# Alarm_Controller_v3.net
KiCad netlist of a schematic drawn in EAGLE
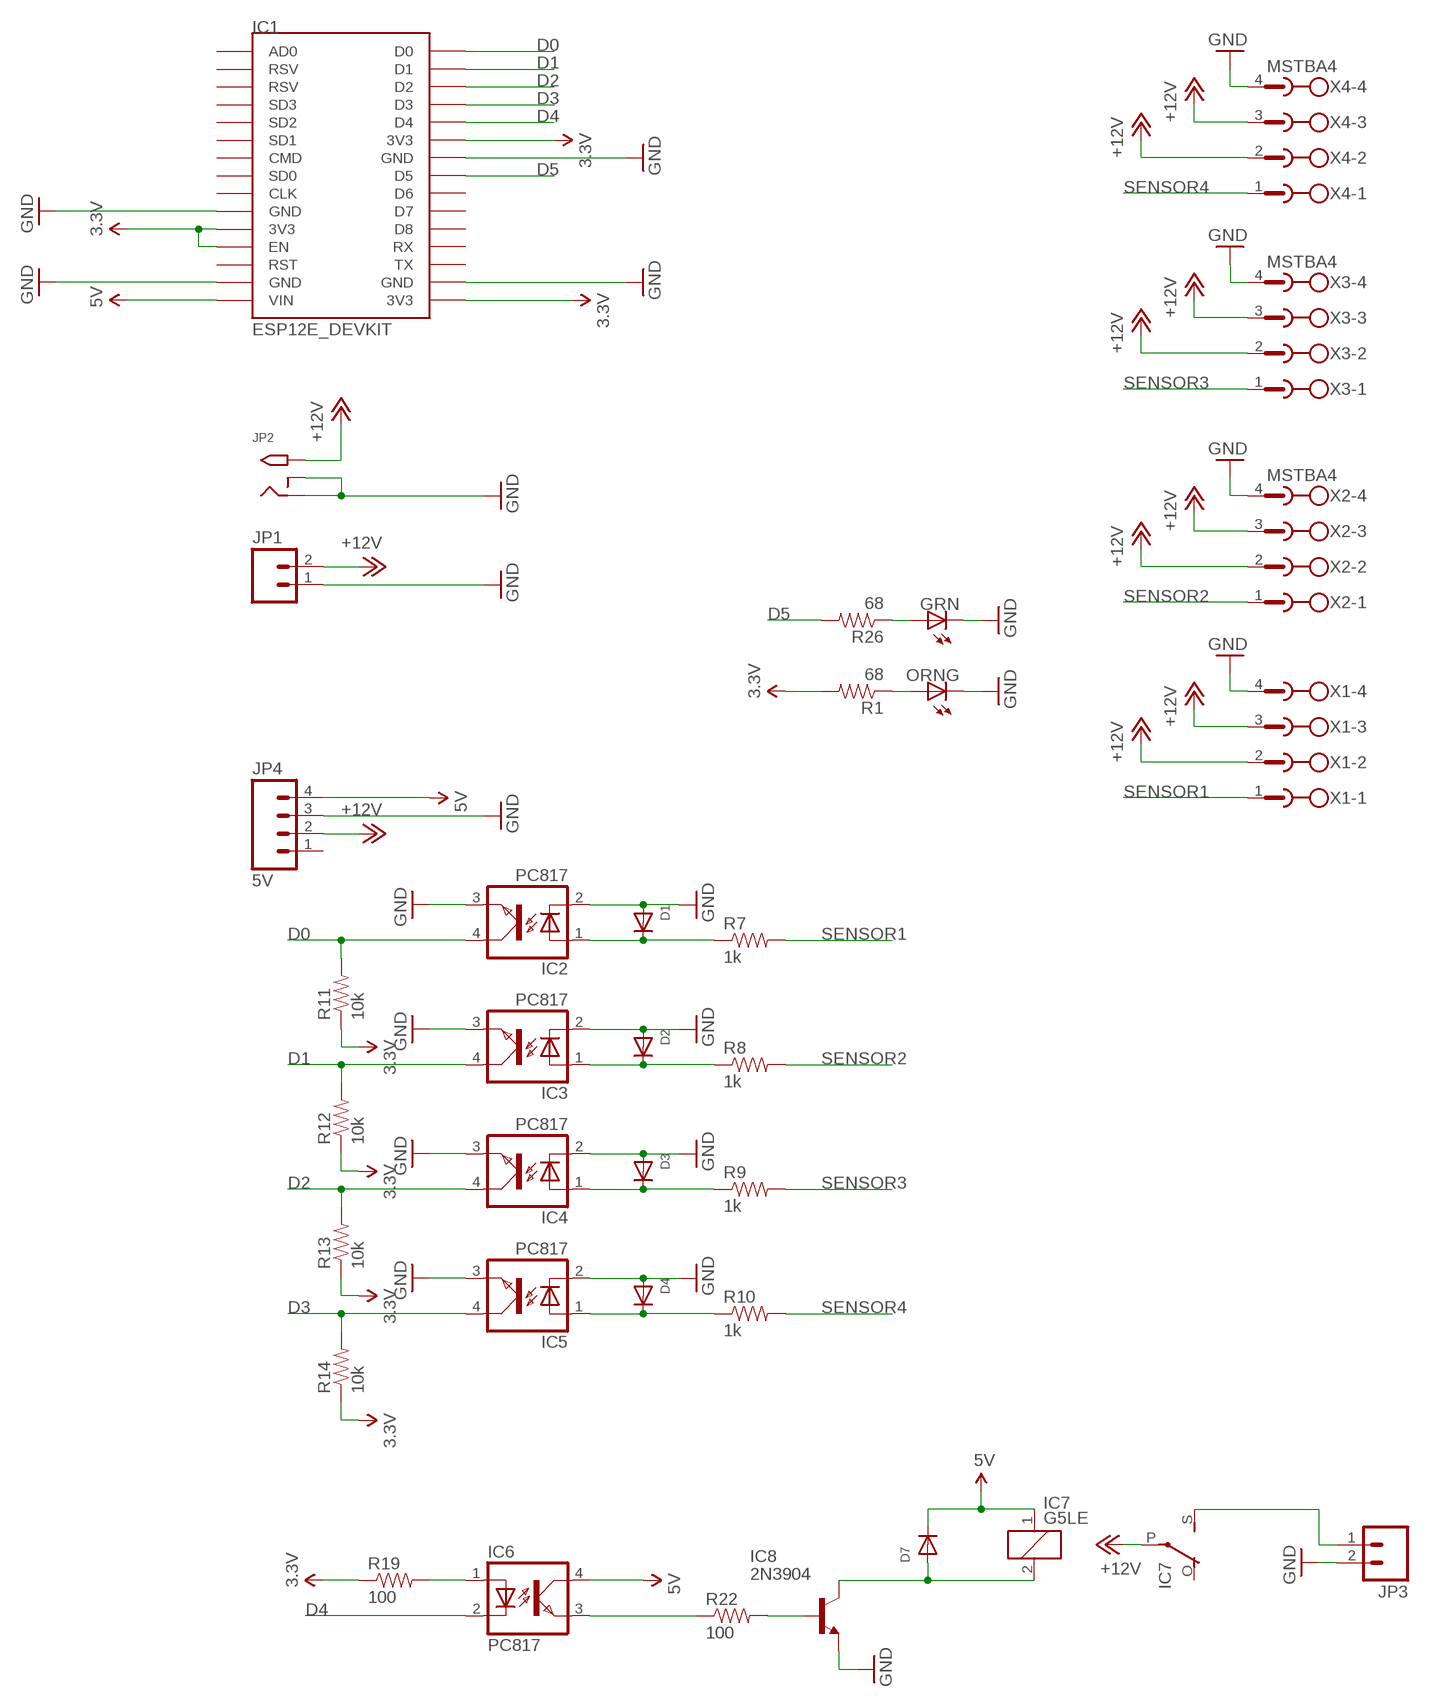
[diagram p0: schematic, sheet 1]

(export (version "E")
  (design (tool "Eeschema 10.0.6"))
  (components
    (comp (ref "D1")
      (value "RB751S-40TE61CT-ND")
      (footprint "eagle-import:SOD-523")
      (libsource (lib "eagle-import") (part "DIODESOD-523"))
    )
    (comp (ref "D2")
      (value "RB751S-40TE61CT-ND")
      (footprint "eagle-import:SOD-523")
      (libsource (lib "eagle-import") (part "DIODESOD-523"))
    )
    (comp (ref "D3")
      (value "RB751S-40TE61CT-ND")
      (footprint "eagle-import:SOD-523")
      (libsource (lib "eagle-import") (part "DIODESOD-523"))
    )
    (comp (ref "D4")
      (value "RB751S-40TE61CT-ND")
      (footprint "eagle-import:SOD-523")
      (libsource (lib "eagle-import") (part "DIODESOD-523"))
    )
    (comp (ref "D7")
      (value "RB751S-40TE61CT-ND")
      (footprint "eagle-import:SOD-523")
      (libsource (lib "eagle-import") (part "DIODESOD-523"))
    )
    (comp (ref "IC1")
      (value "ESP12E_DEVKIT")
      (footprint "eagle-import:ESP12E_DEVKIT")
      (libsource (lib "eagle-import") (part "ESP12E_DEVKIT"))
    )
    (comp (ref "IC2")
      (value "PC817")
      (footprint "eagle-import:DIL04")
      (fields (field (name "MPN") "PC817X4J000F"))
      (libsource (lib "eagle-import") (part "PC817"))
    )
    (comp (ref "IC3")
      (value "PC817")
      (footprint "eagle-import:DIL04")
      (fields (field (name "MPN") "PC817X4J000F"))
      (libsource (lib "eagle-import") (part "PC817"))
    )
    (comp (ref "IC4")
      (value "PC817")
      (footprint "eagle-import:DIL04")
      (fields (field (name "MPN") "PC817X4J000F"))
      (libsource (lib "eagle-import") (part "PC817"))
    )
    (comp (ref "IC5")
      (value "PC817")
      (footprint "eagle-import:DIL04")
      (fields (field (name "MPN") "PC817X4J000F"))
      (libsource (lib "eagle-import") (part "PC817"))
    )
    (comp (ref "IC6")
      (value "PC817")
      (footprint "eagle-import:DIL04")
      (fields (field (name "MPN") "PC817X4J000F"))
      (libsource (lib "eagle-import") (part "PC817"))
    )
    (comp (ref "IC7")
      (value "G5LE")
      (footprint "eagle-import:G5LE")
      (libsource (lib "eagle-import") (part "G5LE"))
    )
    (comp (ref "IC8")
      (value "2N3904")
      (footprint "eagle-import:TO92")
      (libsource (lib "eagle-import") (part "2N3904"))
    )
    (comp (ref "JP1")
      (value "M023.5MM_LOCK")
      (footprint "eagle-import:SCREWTERMINAL-3.5MM-2_LOCK")
      (libsource (lib "eagle-import") (part "M023.5MM_LOCK"))
    )
    (comp (ref "JP2")
      (value "2.1MMJACKTHM")
      (footprint "eagle-import:PJ-102A")
      (libsource (lib "eagle-import") (part "2.1MMJACKTHM"))
    )
    (comp (ref "JP3")
      (value "M023.5MM_LOCK")
      (footprint "eagle-import:SCREWTERMINAL-3.5MM-2_LOCK")
      (libsource (lib "eagle-import") (part "M023.5MM_LOCK"))
    )
    (comp (ref "JP4")
      (value "5V")
      (footprint "eagle-import:1X04_LOCK_LONGPADS")
      (libsource (lib "eagle-import") (part "M04LOCK_LONGPADS"))
    )
    (comp (ref "LED")
      (value "GRN")
      (footprint "eagle-import:SML0805")
      (libsource (lib "eagle-import") (part "LEDSML0805"))
    )
    (comp (ref "LED2")
      (value "ORNG")
      (footprint "eagle-import:SML0805")
      (libsource (lib "eagle-import") (part "LEDSML0805"))
    )
    (comp (ref "R1")
      (value "68")
      (footprint "eagle-import:0603-RES")
      (libsource (lib "eagle-import") (part "RESISTOR0603-RES"))
    )
    (comp (ref "R7")
      (value "1k")
      (footprint "eagle-import:0603-RES")
      (libsource (lib "eagle-import") (part "RESISTOR0603-RES"))
    )
    (comp (ref "R8")
      (value "1k")
      (footprint "eagle-import:0603-RES")
      (libsource (lib "eagle-import") (part "RESISTOR0603-RES"))
    )
    (comp (ref "R9")
      (value "1k")
      (footprint "eagle-import:0603-RES")
      (libsource (lib "eagle-import") (part "RESISTOR0603-RES"))
    )
    (comp (ref "R10")
      (value "1k")
      (footprint "eagle-import:0603-RES")
      (libsource (lib "eagle-import") (part "RESISTOR0603-RES"))
    )
    (comp (ref "R11")
      (value "10k")
      (footprint "eagle-import:0603-RES")
      (libsource (lib "eagle-import") (part "RESISTOR0603-RES"))
    )
    (comp (ref "R12")
      (value "10k")
      (footprint "eagle-import:0603-RES")
      (libsource (lib "eagle-import") (part "RESISTOR0603-RES"))
    )
    (comp (ref "R13")
      (value "10k")
      (footprint "eagle-import:0603-RES")
      (libsource (lib "eagle-import") (part "RESISTOR0603-RES"))
    )
    (comp (ref "R14")
      (value "10k")
      (footprint "eagle-import:0603-RES")
      (libsource (lib "eagle-import") (part "RESISTOR0603-RES"))
    )
    (comp (ref "R19")
      (value "100")
      (footprint "eagle-import:0603-RES")
      (libsource (lib "eagle-import") (part "RESISTOR0603-RES"))
    )
    (comp (ref "R22")
      (value "100")
      (footprint "eagle-import:0603-RES")
      (libsource (lib "eagle-import") (part "RESISTOR0603-RES"))
    )
    (comp (ref "R26")
      (value "68")
      (footprint "eagle-import:0603-RES")
      (libsource (lib "eagle-import") (part "RESISTOR0603-RES"))
    )
    (comp (ref "X1")
      (value "MSTBA4")
      (footprint "eagle-import:MSTBA4")
      (fields (field (name "MF") "FARNELL") (field (name "MPN") "1757268"))
      (libsource (lib "eagle-import") (part "MSTBA4"))
    )
    (comp (ref "X2")
      (value "MSTBA4")
      (footprint "eagle-import:MSTBA4")
      (fields (field (name "MF") "FARNELL") (field (name "MPN") "1757268"))
      (libsource (lib "eagle-import") (part "MSTBA4"))
    )
    (comp (ref "X3")
      (value "MSTBA4")
      (footprint "eagle-import:MSTBA4")
      (fields (field (name "MF") "FARNELL") (field (name "MPN") "1757268"))
      (libsource (lib "eagle-import") (part "MSTBA4"))
    )
    (comp (ref "X4")
      (value "MSTBA4")
      (footprint "eagle-import:MSTBA4")
      (fields (field (name "MF") "FARNELL") (field (name "MPN") "1757268"))
      (libsource (lib "eagle-import") (part "MSTBA4"))
    )
  )
  (nets
    (net (code "1") (name "+12V") (class "Default")
      (node (ref "IC7") (pin "P") (pinfunction "P_P") (pintype "passive"))
      (node (ref "JP1") (pin "2") (pinfunction "2_2") (pintype "passive"))
      (node (ref "JP2") (pin "TIP") (pinfunction "TIP_TIP") (pintype "bidirectional"))
      (node (ref "JP4") (pin "2") (pinfunction "2_2") (pintype "passive"))
      (node (ref "X1") (pin "2") (pinfunction "1_2") (pintype "passive"))
      (node (ref "X1") (pin "3") (pinfunction "1_3") (pintype "passive"))
      (node (ref "X2") (pin "2") (pinfunction "1_2") (pintype "passive"))
      (node (ref "X2") (pin "3") (pinfunction "1_3") (pintype "passive"))
      (node (ref "X3") (pin "2") (pinfunction "1_2") (pintype "passive"))
      (node (ref "X3") (pin "3") (pinfunction "1_3") (pintype "passive"))
      (node (ref "X4") (pin "2") (pinfunction "1_2") (pintype "passive"))
      (node (ref "X4") (pin "3") (pinfunction "1_3") (pintype "passive"))
    )
    (net (code "2") (name "/D0") (class "Default")
      (node (ref "IC1") (pin "D0") (pinfunction "D0_D0") (pintype "bidirectional"))
      (node (ref "IC2") (pin "4") (pinfunction "COL_4") (pintype "passive"))
      (node (ref "R11") (pin "2") (pinfunction "2_2") (pintype "passive"))
    )
    (net (code "3") (name "/D1") (class "Default")
      (node (ref "IC1") (pin "D1") (pinfunction "D1_D1") (pintype "bidirectional"))
      (node (ref "IC3") (pin "4") (pinfunction "COL_4") (pintype "passive"))
      (node (ref "R12") (pin "2") (pinfunction "2_2") (pintype "passive"))
    )
    (net (code "4") (name "/D2") (class "Default")
      (node (ref "IC1") (pin "D2") (pinfunction "D2_D2") (pintype "bidirectional"))
      (node (ref "IC4") (pin "4") (pinfunction "COL_4") (pintype "passive"))
      (node (ref "R13") (pin "2") (pinfunction "2_2") (pintype "passive"))
    )
    (net (code "5") (name "/D3") (class "Default")
      (node (ref "IC1") (pin "D3") (pinfunction "D3_D3") (pintype "bidirectional"))
      (node (ref "IC5") (pin "4") (pinfunction "COL_4") (pintype "passive"))
      (node (ref "R14") (pin "2") (pinfunction "2_2") (pintype "passive"))
    )
    (net (code "6") (name "/D4") (class "Default")
      (node (ref "IC1") (pin "D4") (pinfunction "D4_D4") (pintype "bidirectional"))
      (node (ref "IC6") (pin "2") (pinfunction "C_2") (pintype "passive"))
    )
    (net (code "7") (name "/D5") (class "Default")
      (node (ref "IC1") (pin "D5") (pinfunction "D5_D5") (pintype "bidirectional"))
      (node (ref "R26") (pin "2") (pinfunction "2_2") (pintype "passive"))
    )
    (net (code "8") (name "/SENSOR1") (class "Default")
      (node (ref "R7") (pin "2") (pinfunction "2_2") (pintype "passive"))
      (node (ref "X1") (pin "1") (pinfunction "1_1") (pintype "passive"))
    )
    (net (code "9") (name "/SENSOR2") (class "Default")
      (node (ref "R8") (pin "2") (pinfunction "2_2") (pintype "passive"))
      (node (ref "X2") (pin "1") (pinfunction "1_1") (pintype "passive"))
    )
    (net (code "10") (name "/SENSOR3") (class "Default")
      (node (ref "R9") (pin "2") (pinfunction "2_2") (pintype "passive"))
      (node (ref "X3") (pin "1") (pinfunction "1_1") (pintype "passive"))
    )
    (net (code "11") (name "/SENSOR4") (class "Default")
      (node (ref "R10") (pin "2") (pinfunction "2_2") (pintype "passive"))
      (node (ref "X4") (pin "1") (pinfunction "1_1") (pintype "passive"))
    )
    (net (code "12") (name "3.3V") (class "Default")
      (node (ref "IC1") (pin "3V3@0") (pinfunction "3V3_3V3@0") (pintype "bidirectional"))
      (node (ref "IC1") (pin "3V3@1") (pinfunction "3V3_3V3@1") (pintype "bidirectional"))
      (node (ref "IC1") (pin "3V3@2") (pinfunction "3V3_3V3@2") (pintype "bidirectional"))
      (node (ref "IC1") (pin "EN") (pinfunction "EN_EN") (pintype "bidirectional"))
      (node (ref "R1") (pin "2") (pinfunction "2_2") (pintype "passive"))
      (node (ref "R11") (pin "1") (pinfunction "1_1") (pintype "passive"))
      (node (ref "R12") (pin "1") (pinfunction "1_1") (pintype "passive"))
      (node (ref "R13") (pin "1") (pinfunction "1_1") (pintype "passive"))
      (node (ref "R14") (pin "1") (pinfunction "1_1") (pintype "passive"))
      (node (ref "R19") (pin "1") (pinfunction "1_1") (pintype "passive"))
    )
    (net (code "13") (name "5V") (class "Default")
      (node (ref "D7") (pin "K") (pinfunction "C_K") (pintype "passive"))
      (node (ref "IC1") (pin "VIN") (pinfunction "VIN_VIN") (pintype "bidirectional"))
      (node (ref "IC6") (pin "4") (pinfunction "COL_4") (pintype "passive"))
      (node (ref "IC7") (pin "1") (pinfunction "1_1") (pintype "passive"))
      (node (ref "JP4") (pin "4") (pinfunction "4_4") (pintype "passive"))
    )
    (net (code "14") (name "GND") (class "Default")
      (node (ref "D1") (pin "A") (pinfunction "A_A") (pintype "passive"))
      (node (ref "D2") (pin "A") (pinfunction "A_A") (pintype "passive"))
      (node (ref "D3") (pin "A") (pinfunction "A_A") (pintype "passive"))
      (node (ref "D4") (pin "A") (pinfunction "A_A") (pintype "passive"))
      (node (ref "IC1") (pin "GND@0") (pinfunction "GND_GND@0") (pintype "bidirectional"))
      (node (ref "IC1") (pin "GND@1") (pinfunction "GND_GND@1") (pintype "bidirectional"))
      (node (ref "IC1") (pin "GND@2") (pinfunction "GND_GND@2") (pintype "bidirectional"))
      (node (ref "IC1") (pin "GND@3") (pinfunction "GND_GND@3") (pintype "bidirectional"))
      (node (ref "IC2") (pin "2") (pinfunction "C_2") (pintype "passive"))
      (node (ref "IC2") (pin "3") (pinfunction "EMIT_3") (pintype "passive"))
      (node (ref "IC3") (pin "2") (pinfunction "C_2") (pintype "passive"))
      (node (ref "IC3") (pin "3") (pinfunction "EMIT_3") (pintype "passive"))
      (node (ref "IC4") (pin "2") (pinfunction "C_2") (pintype "passive"))
      (node (ref "IC4") (pin "3") (pinfunction "EMIT_3") (pintype "passive"))
      (node (ref "IC5") (pin "2") (pinfunction "C_2") (pintype "passive"))
      (node (ref "IC5") (pin "3") (pinfunction "EMIT_3") (pintype "passive"))
      (node (ref "IC8") (pin "3") (pinfunction "E_3") (pintype "passive"))
      (node (ref "JP1") (pin "1") (pinfunction "1_1") (pintype "passive"))
      (node (ref "JP2") (pin "RING") (pinfunction "RING_RING") (pintype "bidirectional"))
      (node (ref "JP2") (pin "RING_SW") (pinfunction "RING_SW_RING_SW") (pintype "bidirectional"))
      (node (ref "JP3") (pin "2") (pinfunction "2_2") (pintype "passive"))
      (node (ref "JP4") (pin "3") (pinfunction "3_3") (pintype "passive"))
      (node (ref "LED") (pin "C") (pinfunction "C_C") (pintype "passive"))
      (node (ref "LED2") (pin "C") (pinfunction "C_C") (pintype "passive"))
      (node (ref "X1") (pin "4") (pinfunction "1_4") (pintype "passive"))
      (node (ref "X2") (pin "4") (pinfunction "1_4") (pintype "passive"))
      (node (ref "X3") (pin "4") (pinfunction "1_4") (pintype "passive"))
      (node (ref "X4") (pin "4") (pinfunction "1_4") (pintype "passive"))
    )
    (net (code "15") (name "Net-(D1-C)") (class "Default")
      (node (ref "D1") (pin "K") (pinfunction "C_K") (pintype "passive"))
      (node (ref "IC2") (pin "1") (pinfunction "A_1") (pintype "passive"))
      (node (ref "R7") (pin "1") (pinfunction "1_1") (pintype "passive"))
    )
    (net (code "16") (name "Net-(D2-C)") (class "Default")
      (node (ref "D2") (pin "K") (pinfunction "C_K") (pintype "passive"))
      (node (ref "IC3") (pin "1") (pinfunction "A_1") (pintype "passive"))
      (node (ref "R8") (pin "1") (pinfunction "1_1") (pintype "passive"))
    )
    (net (code "17") (name "Net-(D3-C)") (class "Default")
      (node (ref "D3") (pin "K") (pinfunction "C_K") (pintype "passive"))
      (node (ref "IC4") (pin "1") (pinfunction "A_1") (pintype "passive"))
      (node (ref "R9") (pin "1") (pinfunction "1_1") (pintype "passive"))
    )
    (net (code "18") (name "Net-(D4-C)") (class "Default")
      (node (ref "D4") (pin "K") (pinfunction "C_K") (pintype "passive"))
      (node (ref "IC5") (pin "1") (pinfunction "A_1") (pintype "passive"))
      (node (ref "R10") (pin "1") (pinfunction "1_1") (pintype "passive"))
    )
    (net (code "19") (name "Net-(IC6-A)") (class "Default")
      (node (ref "IC6") (pin "1") (pinfunction "A_1") (pintype "passive"))
      (node (ref "R19") (pin "2") (pinfunction "2_2") (pintype "passive"))
    )
    (net (code "20") (name "Net-(IC6-EMIT)") (class "Default")
      (node (ref "IC6") (pin "3") (pinfunction "EMIT_3") (pintype "passive"))
      (node (ref "R22") (pin "1") (pinfunction "1_1") (pintype "passive"))
    )
    (net (code "21") (name "Net-(IC7-PadS)") (class "Default")
      (node (ref "IC7") (pin "S") (pinfunction "S_S") (pintype "passive"))
      (node (ref "JP3") (pin "1") (pinfunction "1_1") (pintype "passive"))
    )
    (net (code "22") (name "Net-(IC8-B)") (class "Default")
      (node (ref "IC8") (pin "2") (pinfunction "B_2") (pintype "passive"))
      (node (ref "R22") (pin "2") (pinfunction "2_2") (pintype "passive"))
    )
    (net (code "23") (name "Net-(IC8-C)") (class "Default")
      (node (ref "D7") (pin "A") (pinfunction "A_A") (pintype "passive"))
      (node (ref "IC7") (pin "2") (pinfunction "2_2") (pintype "passive"))
      (node (ref "IC8") (pin "1") (pinfunction "C_1") (pintype "passive"))
    )
    (net (code "24") (name "Net-(LED-PadA)") (class "Default")
      (node (ref "LED") (pin "A") (pinfunction "A_A") (pintype "passive"))
      (node (ref "R26") (pin "1") (pinfunction "1_1") (pintype "passive"))
    )
    (net (code "25") (name "Net-(LED2-PadA)") (class "Default")
      (node (ref "LED2") (pin "A") (pinfunction "A_A") (pintype "passive"))
      (node (ref "R1") (pin "1") (pinfunction "1_1") (pintype "passive"))
    )
    (net (code "26") (name "unconnected-(IC1-PadAD0)") (class "Default")
      (node (ref "IC1") (pin "AD0") (pinfunction "AD0_AD0") (pintype "bidirectional"))
    )
    (net (code "27") (name "unconnected-(IC1-PadCLK)") (class "Default")
      (node (ref "IC1") (pin "CLK") (pinfunction "CLK_CLK") (pintype "bidirectional"))
    )
    (net (code "28") (name "unconnected-(IC1-PadCMD)") (class "Default")
      (node (ref "IC1") (pin "CMD") (pinfunction "CMD_CMD") (pintype "bidirectional"))
    )
    (net (code "29") (name "unconnected-(IC1-PadD6)") (class "Default")
      (node (ref "IC1") (pin "D6") (pinfunction "D6_D6") (pintype "bidirectional"))
    )
    (net (code "30") (name "unconnected-(IC1-PadD7)") (class "Default")
      (node (ref "IC1") (pin "D7") (pinfunction "D7_D7") (pintype "bidirectional"))
    )
    (net (code "31") (name "unconnected-(IC1-PadD8)") (class "Default")
      (node (ref "IC1") (pin "D8") (pinfunction "D8_D8") (pintype "bidirectional"))
    )
    (net (code "32") (name "unconnected-(IC1-PadRST)") (class "Default")
      (node (ref "IC1") (pin "RST") (pinfunction "RST_RST") (pintype "bidirectional"))
    )
    (net (code "33") (name "unconnected-(IC1-PadRX)") (class "Default")
      (node (ref "IC1") (pin "RX") (pinfunction "RX_RX") (pintype "bidirectional"))
    )
    (net (code "34") (name "unconnected-(IC1-PadSD0)") (class "Default")
      (node (ref "IC1") (pin "SD0") (pinfunction "SD0_SD0") (pintype "bidirectional"))
    )
    (net (code "35") (name "unconnected-(IC1-PadSD1)") (class "Default")
      (node (ref "IC1") (pin "SD1") (pinfunction "SD1_SD1") (pintype "bidirectional"))
    )
    (net (code "36") (name "unconnected-(IC1-PadSD2)") (class "Default")
      (node (ref "IC1") (pin "SD2") (pinfunction "SD2_SD2") (pintype "bidirectional"))
    )
    (net (code "37") (name "unconnected-(IC1-PadSD3)") (class "Default")
      (node (ref "IC1") (pin "SD3") (pinfunction "SD3_SD3") (pintype "bidirectional"))
    )
    (net (code "38") (name "unconnected-(IC1-PadTX)") (class "Default")
      (node (ref "IC1") (pin "TX") (pinfunction "TX_TX") (pintype "bidirectional"))
    )
    (net (code "39") (name "unconnected-(IC1-RSV-PadRSV@0)") (class "Default")
      (node (ref "IC1") (pin "RSV@0") (pinfunction "RSV_RSV@0") (pintype "bidirectional"))
    )
    (net (code "40") (name "unconnected-(IC1-RSV-PadRSV@1)") (class "Default")
      (node (ref "IC1") (pin "RSV@1") (pinfunction "RSV_RSV@1") (pintype "bidirectional"))
    )
    (net (code "41") (name "unconnected-(IC7-PadO)") (class "Default")
      (node (ref "IC7") (pin "O") (pinfunction "O_O") (pintype "passive"))
    )
    (net (code "42") (name "unconnected-(JP4-Pad1)") (class "Default")
      (node (ref "JP4") (pin "1") (pinfunction "1_1") (pintype "passive"))
    )
  )
)
